# debug.net
KiCad netlist of a schematic drawn in Altium Designer
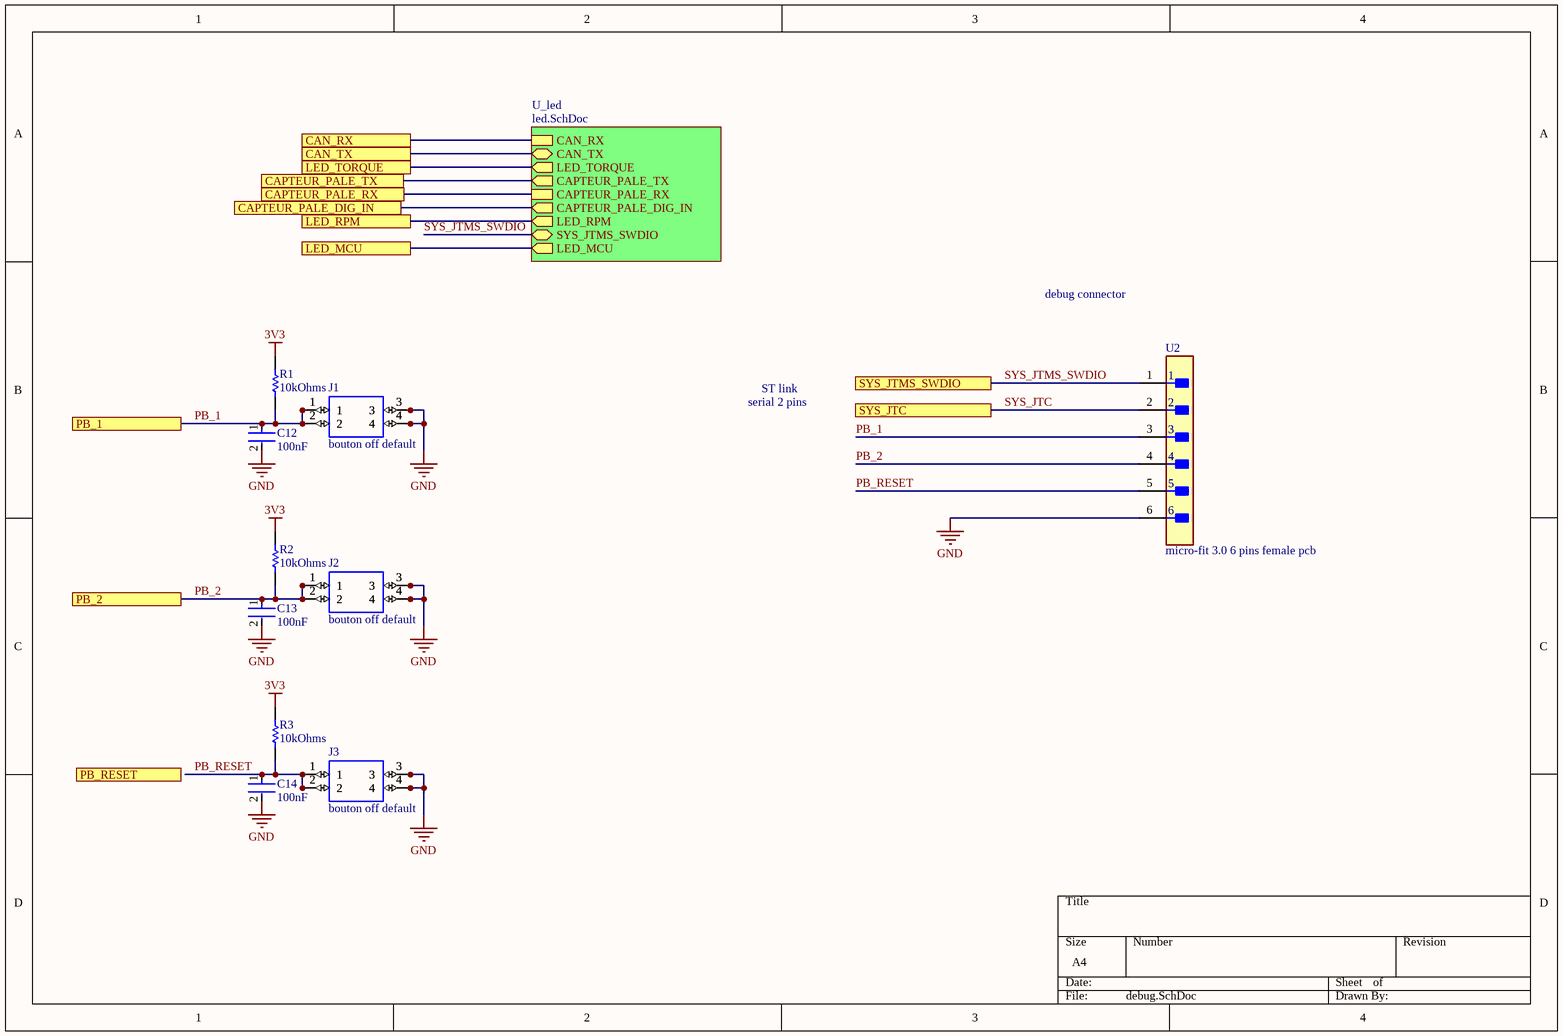
[diagram p0: debug.SchDoc]

(export (version "E")
  (design (tool "Eeschema 10.0.6"))
  (components
    (comp (ref "C12")
      (value "100nF")
      (footprint "FP-CL278-IPC_A")
      (description "Multilayer Ceramic Capacitor, 0.1 uF, 25 V, ± 10%, X5R, 0402 [1005 Metric]")
      (fields
        (field (name "MANUFACTURER") "Samsung")
        (field (name "MANUFACTURER PART NUMBER") "CL05A104KA5NNNC")
      )
      (libsource (lib "chinook_lib_symbol_rotor") (part "CL05A104KA5NNNC"))
    )
    (comp (ref "C13")
      (value "100nF")
      (footprint "FP-CL278-IPC_A")
      (description "Multilayer Ceramic Capacitor, 0.1 uF, 25 V, ± 10%, X5R, 0402 [1005 Metric]")
      (fields
        (field (name "MANUFACTURER") "Samsung")
        (field (name "MANUFACTURER PART NUMBER") "CL05A104KA5NNNC")
      )
      (libsource (lib "chinook_lib_symbol_rotor") (part "CL05A104KA5NNNC"))
    )
    (comp (ref "C14")
      (value "100nF")
      (footprint "FP-CL278-IPC_A")
      (description "Multilayer Ceramic Capacitor, 0.1 uF, 25 V, ± 10%, X5R, 0402 [1005 Metric]")
      (fields
        (field (name "MANUFACTURER") "Samsung")
        (field (name "MANUFACTURER PART NUMBER") "CL05A104KA5NNNC")
      )
      (libsource (lib "chinook_lib_symbol_rotor") (part "CL05A104KA5NNNC"))
    )
    (comp (ref "J1")
      (value "bouton off default")
      (footprint "PTS810SJG250SMTRLFS")
      (description "Switch Tactile N.O. SPST Button J-Bend 0.05A 16VDC 50000Cycle 2.55N SMD T/R")
      (fields
        (field (name "MANUFACTURER") "ITT C&K")
        (field (name "MANUFACTURER PART NUMBER") "PTS810SJK250SMTRLFS")
      )
      (libsource (lib "chinook_lib_symbol_rotor") (part "PTS810SJK250SMTRLFS"))
    )
    (comp (ref "J2")
      (value "bouton off default")
      (footprint "PTS810SJG250SMTRLFS")
      (description "Switch Tactile N.O. SPST Button J-Bend 0.05A 16VDC 50000Cycle 2.55N SMD T/R")
      (fields
        (field (name "MANUFACTURER") "ITT C&K")
        (field (name "MANUFACTURER PART NUMBER") "PTS810SJK250SMTRLFS")
      )
      (libsource (lib "chinook_lib_symbol_rotor") (part "PTS810SJK250SMTRLFS"))
    )
    (comp (ref "J3")
      (value "bouton off default")
      (footprint "PTS810SJG250SMTRLFS")
      (description "Switch Tactile N.O. SPST Button J-Bend 0.05A 16VDC 50000Cycle 2.55N SMD T/R")
      (fields
        (field (name "MANUFACTURER") "ITT C&K")
        (field (name "MANUFACTURER PART NUMBER") "PTS810SJK250SMTRLFS")
      )
      (libsource (lib "chinook_lib_symbol_rotor") (part "PTS810SJK250SMTRLFS"))
    )
    (comp (ref "R1")
      (value "10kOhms")
      (footprint "FP-RC1005-MFG")
      (description "Res Thick Film 0402 10K Ohm 1% 1/16W ±100ppm/°C Molded SMD SMD T/R")
      (fields
        (field (name "MANUFACTURER") "Samsung")
        (field (name "MANUFACTURER PART NUMBER") "RC1005F103CS")
      )
      (libsource (lib "chinook_lib_symbol_rotor") (part "RC1005F103CS"))
    )
    (comp (ref "R2")
      (value "10kOhms")
      (footprint "FP-RC1005-MFG")
      (description "Res Thick Film 0402 10K Ohm 1% 1/16W ±100ppm/°C Molded SMD SMD T/R")
      (fields
        (field (name "MANUFACTURER") "Samsung")
        (field (name "MANUFACTURER PART NUMBER") "RC1005F103CS")
      )
      (libsource (lib "chinook_lib_symbol_rotor") (part "RC1005F103CS"))
    )
    (comp (ref "R3")
      (value "10kOhms")
      (footprint "FP-RC1005-MFG")
      (description "Res Thick Film 0402 10K Ohm 1% 1/16W ±100ppm/°C Molded SMD SMD T/R")
      (fields
        (field (name "MANUFACTURER") "Samsung")
        (field (name "MANUFACTURER PART NUMBER") "RC1005F103CS")
      )
      (libsource (lib "chinook_lib_symbol_rotor") (part "RC1005F103CS"))
    )
    (comp (ref "U2")
      (value "micro-fit 3.0 6 pins female pcb")
      (footprint "FP-0430450600-MFG")
      (description "Connector Wire to Board Header 6 Position 3mm Solder Right Angle Thru-Hole Tray")
      (fields (field (name "MANUFACTURER") "Molex") (field (name "MANUFACTURER PART NUMBER") "43045-0600"))
      (libsource (lib "chinook_lib_symbol_rotor") (part "430450600"))
    )
  )
  (nets
    (net (code "9") (name "/PB_1") (class "Default")
      (node (ref "C12") (pin "1") (pinfunction "1_1") (pintype "passive"))
      (node (ref "J1") (pin "1") (pinfunction "1_1") (pintype "bidirectional"))
      (node (ref "J1") (pin "2") (pinfunction "2_2") (pintype "bidirectional"))
      (node (ref "R1") (pin "1") (pinfunction "1_1") (pintype "passive"))
      (node (ref "U2") (pin "3") (pinfunction "3_3") (pintype "passive"))
    )
    (net (code "10") (name "/PB_2") (class "Default")
      (node (ref "C13") (pin "1") (pinfunction "1_1") (pintype "passive"))
      (node (ref "J2") (pin "1") (pinfunction "1_1") (pintype "bidirectional"))
      (node (ref "J2") (pin "2") (pinfunction "2_2") (pintype "bidirectional"))
      (node (ref "R2") (pin "1") (pinfunction "1_1") (pintype "passive"))
      (node (ref "U2") (pin "4") (pinfunction "4_4") (pintype "passive"))
    )
    (net (code "11") (name "/PB_RESET") (class "Default")
      (node (ref "C14") (pin "1") (pinfunction "1_1") (pintype "passive"))
      (node (ref "J3") (pin "1") (pinfunction "1_1") (pintype "bidirectional"))
      (node (ref "J3") (pin "2") (pinfunction "2_2") (pintype "bidirectional"))
      (node (ref "R3") (pin "1") (pinfunction "1_1") (pintype "passive"))
      (node (ref "U2") (pin "5") (pinfunction "5_5") (pintype "passive"))
    )
    (net (code "12") (name "/SYS_JTC") (class "Default")
      (node (ref "U2") (pin "2") (pinfunction "2_2") (pintype "passive"))
    )
    (net (code "13") (name "/SYS_JTMS_SWDIO") (class "Default")
      (node (ref "U2") (pin "1") (pinfunction "1_1") (pintype "passive"))
    )
    (net (code "14") (name "3V3") (class "Default")
      (node (ref "R1") (pin "2") (pinfunction "2_2") (pintype "passive"))
      (node (ref "R2") (pin "2") (pinfunction "2_2") (pintype "passive"))
      (node (ref "R3") (pin "2") (pinfunction "2_2") (pintype "passive"))
    )
    (net (code "15") (name "GND") (class "Default")
      (node (ref "C12") (pin "2") (pinfunction "2_2") (pintype "passive"))
      (node (ref "C13") (pin "2") (pinfunction "2_2") (pintype "passive"))
      (node (ref "C14") (pin "2") (pinfunction "2_2") (pintype "passive"))
      (node (ref "J1") (pin "3") (pinfunction "3_3") (pintype "bidirectional"))
      (node (ref "J1") (pin "4") (pinfunction "4_4") (pintype "bidirectional"))
      (node (ref "J2") (pin "3") (pinfunction "3_3") (pintype "bidirectional"))
      (node (ref "J2") (pin "4") (pinfunction "4_4") (pintype "bidirectional"))
      (node (ref "J3") (pin "3") (pinfunction "3_3") (pintype "bidirectional"))
      (node (ref "J3") (pin "4") (pinfunction "4_4") (pintype "bidirectional"))
      (node (ref "U2") (pin "6") (pinfunction "6_6") (pintype "passive"))
    )
  )
)
